# B6_32D_20230729.net
KiCad netlist of a schematic drawn in Altium Designer
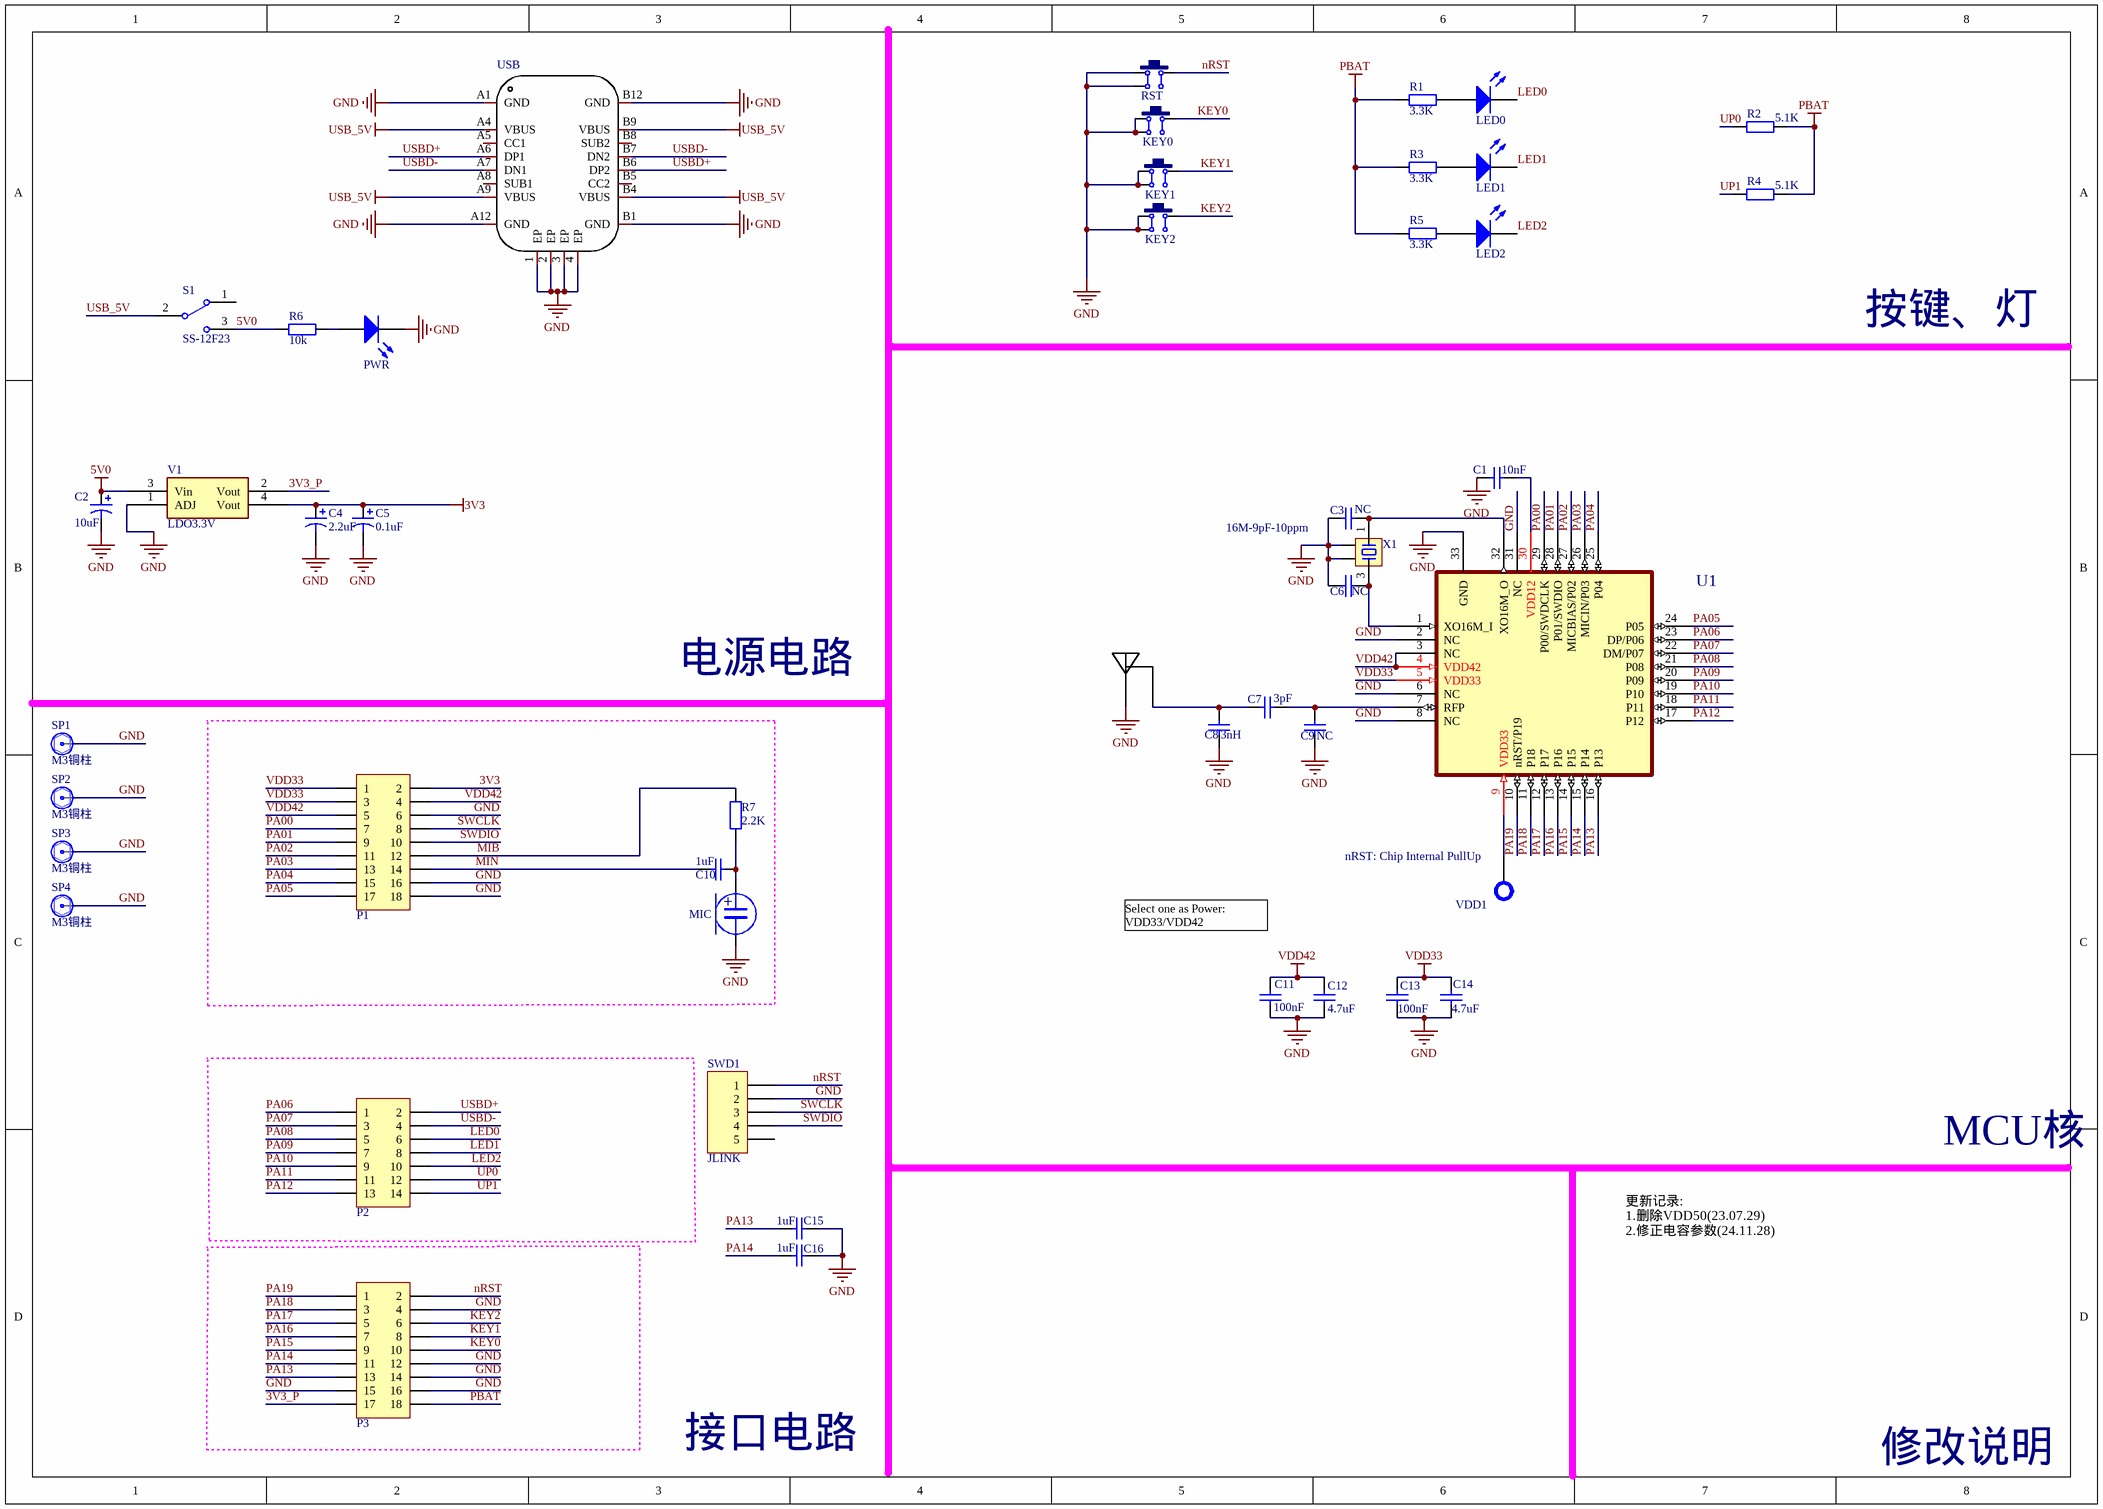
[diagram p0: B6_32D_20230729.SchDoc]

(export (version "E")
  (design (tool "Eeschema 10.0.6"))
  (components
    (comp (ref "ANT1")
      (value "ANT1")
      (footprint "常用2.4G天线7")
      (libsource (lib "HYBXX_Dragon") (part "ANT_PCB2"))
    )
    (comp (ref "C1")
      (value "10nF")
      (footprint "C0603")
      (description "Capacitor (Semiconductor SIM Model)")
      (libsource (lib "HYBXX_Dragon") (part "Cap"))
    )
    (comp (ref "C2")
      (value "10uF")
      (footprint "HYBXX_Dragon:C0603")
      (description "Polarized Capacitor (Surface Mount)")
      (fields (field (name "PUBLISHER") "Altium Limited"))
      (libsource (lib "HYBXX_Dragon") (part "Cap Pol3"))
    )
    (comp (ref "C3")
      (value "NC")
      (footprint "C0603")
      (description "Capacitor (Semiconductor SIM Model)")
      (libsource (lib "HYBXX_Dragon") (part "Cap"))
    )
    (comp (ref "C4")
      (value "2.2uF")
      (footprint "HYBXX_Dragon:C0603")
      (description "Polarized Capacitor (Surface Mount)")
      (fields (field (name "PUBLISHER") "Altium Limited"))
      (libsource (lib "HYBXX_Dragon") (part "Cap Pol3"))
    )
    (comp (ref "C5")
      (value "0.1uF")
      (footprint "HYBXX_Dragon:C0603")
      (description "Polarized Capacitor (Surface Mount)")
      (fields (field (name "PUBLISHER") "Altium Limited"))
      (libsource (lib "HYBXX_Dragon") (part "Cap Pol3"))
    )
    (comp (ref "C6")
      (value "NC")
      (footprint "C0603")
      (description "Capacitor (Semiconductor SIM Model)")
      (libsource (lib "HYBXX_Dragon") (part "Cap"))
    )
    (comp (ref "C7")
      (value "3pF")
      (footprint "C0402")
      (description "Capacitor (Semiconductor SIM Model)")
      (libsource (lib "HYBXX_Dragon") (part "Cap"))
    )
    (comp (ref "C8")
      (value "3nH")
      (footprint "C0402")
      (description "Capacitor (Semiconductor SIM Model)")
      (libsource (lib "HYBXX_Dragon") (part "Cap"))
    )
    (comp (ref "C9")
      (value "NC")
      (footprint "C0402")
      (description "Capacitor (Semiconductor SIM Model)")
      (libsource (lib "HYBXX_Dragon") (part "Cap"))
    )
    (comp (ref "C10")
      (value "1uF")
      (footprint "C0603")
      (description "Capacitor (Semiconductor SIM Model)")
      (libsource (lib "HYBXX_Dragon") (part "Cap"))
    )
    (comp (ref "C11")
      (value "100nF")
      (footprint "C0603")
      (description "Capacitor (Semiconductor SIM Model)")
      (libsource (lib "HYBXX_Dragon") (part "Cap"))
    )
    (comp (ref "C12")
      (value "4.7uF")
      (footprint "C0603")
      (description "Capacitor (Semiconductor SIM Model)")
      (libsource (lib "HYBXX_Dragon") (part "Cap"))
    )
    (comp (ref "C13")
      (value "100nF")
      (footprint "C0603")
      (description "Capacitor (Semiconductor SIM Model)")
      (fields (field (name "PUBLISHER") "Altium Limited"))
      (libsource (lib "Miscellaneous Devices") (part "Cap Semi"))
    )
    (comp (ref "C14")
      (value "4.7uF")
      (footprint "C0603")
      (description "Capacitor (Semiconductor SIM Model)")
      (libsource (lib "HYBXX_Dragon") (part "Cap"))
    )
    (comp (ref "C15")
      (value "1uF")
      (footprint "C0603")
      (description "Capacitor (Semiconductor SIM Model)")
      (libsource (lib "HYBXX_Dragon") (part "Cap"))
    )
    (comp (ref "C16")
      (value "1uF")
      (footprint "C0603")
      (description "Capacitor (Semiconductor SIM Model)")
      (libsource (lib "HYBXX_Dragon") (part "Cap"))
    )
    (comp (ref "KEY0")
      (value "6x6x5")
      (footprint "SW-SMD")
      (description "贴片6x6轻触开关")
      (fields (field (name "版权归属") "封装库来自淘宝 ID：黄晶宝石"))
      (libsource (lib "0.7 - 常用按键-开关") (part "TSW SMD-6x6"))
    )
    (comp (ref "KEY1")
      (value "6x6x5")
      (footprint "SW-SMD")
      (description "贴片6x6轻触开关")
      (fields (field (name "版权归属") "封装库来自淘宝 ID：黄晶宝石"))
      (libsource (lib "0.7 - 常用按键-开关") (part "TSW SMD-6x6"))
    )
    (comp (ref "KEY2")
      (value "6x6x5")
      (footprint "SW-SMD")
      (description "贴片6x6轻触开关")
      (fields (field (name "版权归属") "封装库来自淘宝 ID：黄晶宝石"))
      (libsource (lib "0.7 - 常用按键-开关") (part "TSW SMD-6x6"))
    )
    (comp (ref "LED0")
      (value "*")
      (footprint "LED_0603")
      (description "发光二极管")
      (libsource (lib "HYBXX_Dragon") (part "LED"))
    )
    (comp (ref "LED1")
      (value "*")
      (footprint "LED_0603")
      (description "发光二极管")
      (libsource (lib "HYBXX_Dragon") (part "LED"))
    )
    (comp (ref "LED2")
      (value "*")
      (footprint "LED_0603")
      (description "发光二极管")
      (libsource (lib "HYBXX_Dragon") (part "LED"))
    )
    (comp (ref "MIC")
      (value "MIC-6*5mm")
      (footprint "MIC-6*5.5mm")
      (description "电容麦克风")
      (fields (field (name "版权归属") "封装库来自淘宝 ID：黄晶宝石"))
      (libsource (lib "1.2 - 传感元件") (part "MIC1"))
    )
    (comp (ref "P1")
      (value "Header 2X11")
      (footprint "HDR2.54-LI-2x9P")
      (description "9*2P接插件")
      (fields (field (name "版权归属") "淘宝ID:黄晶宝石"))
      (libsource (lib "5.3 - 接插件-脚距2.54 (100mil) ") (part "Header 9X2"))
    )
    (comp (ref "P2")
      (value "Header 2X7")
      (footprint "HDR2.54-LI-2x7P")
      (description "7*2P接插件")
      (fields (field (name "版权归属") "封装库来自淘宝 ID：黄晶宝石"))
      (libsource (lib "5.3 - 接插件-脚距2.54 (100mil) ") (part "Header 7X2"))
    )
    (comp (ref "P3")
      (value "Header 2X11")
      (footprint "HDR2.54-LI-2x9P")
      (description "9*2P接插件")
      (fields (field (name "版权归属") "淘宝ID:黄晶宝石"))
      (libsource (lib "5.3 - 接插件-脚距2.54 (100mil) ") (part "Header 9X2"))
    )
    (comp (ref "PWR")
      (value "*")
      (footprint "LED_0603")
      (description "发光二极管")
      (libsource (lib "HYBXX_Dragon") (part "LED"))
    )
    (comp (ref "R1")
      (value "3.3K")
      (footprint "R 0603_L")
      (description "贴片电阻")
      (libsource (lib "HYBXX_Dragon") (part "Res"))
    )
    (comp (ref "R2")
      (value "5.1K")
      (footprint "R 0603_L")
      (description "贴片电阻")
      (libsource (lib "") (part "Res_1"))
    )
    (comp (ref "R3")
      (value "3.3K")
      (footprint "R 0603_L")
      (description "贴片电阻")
      (libsource (lib "HYBXX_Dragon") (part "Res"))
    )
    (comp (ref "R4")
      (value "5.1K")
      (footprint "R 0603_L")
      (description "贴片电阻")
      (libsource (lib "") (part "Res_1"))
    )
    (comp (ref "R5")
      (value "3.3K")
      (footprint "R 0603_L")
      (description "贴片电阻")
      (libsource (lib "HYBXX_Dragon") (part "Res"))
    )
    (comp (ref "R6")
      (value "10k")
      (footprint "RESC_0603")
      (description "贴片电阻")
      (libsource (lib "HYBXX_Dragon") (part "Res"))
    )
    (comp (ref "R7")
      (value "2.2K")
      (footprint "R 0603_L")
      (description "贴片电阻")
      (libsource (lib "") (part "Res_1"))
    )
    (comp (ref "RST")
      (value "6x6x5")
      (footprint "SW-SMD")
      (description "贴片6x6轻触开关")
      (fields (field (name "版权归属") "封装库来自淘宝 ID：黄晶宝石"))
      (libsource (lib "0.7 - 常用按键-开关") (part "TSW SMD-6x6"))
    )
    (comp (ref "S1")
      (value "SS-12F23")
      (footprint "SK12D07VG3")
      (description "1路波动开关")
      (fields (field (name "版权归属") "封装库来自淘宝 ID：黄晶宝石"))
      (libsource (lib "0.7 - 常用按键-开关") (part "SSW-1P"))
    )
    (comp (ref "SP1")
      (value "M3铜柱")
      (footprint "M3x21+6_L")
      (description "铜柱")
      (libsource (lib "4.1 - 未分类器件") (part "铜柱加头小焊盘"))
    )
    (comp (ref "SP2")
      (value "M3铜柱")
      (footprint "M3x21+6_L")
      (description "铜柱")
      (fields (field (name "版权归属") "封装库来自淘宝 ID：黄晶宝石"))
      (libsource (lib "4.1 - 未分类器件") (part "铜柱加头小焊盘"))
    )
    (comp (ref "SP3")
      (value "M3铜柱")
      (footprint "M3x21+6_L")
      (description "铜柱")
      (fields (field (name "版权归属") "封装库来自淘宝 ID：黄晶宝石"))
      (libsource (lib "4.1 - 未分类器件") (part "铜柱加头小焊盘"))
    )
    (comp (ref "SP4")
      (value "M3铜柱")
      (footprint "M3x21+6_L")
      (description "铜柱")
      (fields (field (name "版权归属") "封装库来自淘宝 ID：黄晶宝石"))
      (libsource (lib "4.1 - 未分类器件") (part "铜柱加头小焊盘"))
    )
    (comp (ref "SWD1")
      (value "JLINK")
      (footprint "HDR2.54-LI-5P")
      (description "Header, 5-Pin")
      (fields (field (name "PUBLISHER") "Altium Limited"))
      (libsource (lib "5.3 - 接插件-脚距2.54 (100mil) ") (part "Header 5"))
    )
    (comp (ref "U1")
      (value "C1_QFN32")
      (footprint "QFN32L_0404x0.75-0.40")
      (description "HY Dragon C 蓝牙芯片, QFN32_4x4")
      (libsource (lib "HYBXX_Dragon") (part "C1_QFN32"))
    )
    (comp (ref "USB")
      (value "KH-TYPE-C-16P")
      (footprint "USB-C-SMD_KH-TYPE-C-16P")
      (description "连接器类型:Type-C;标准:-;公母:母座;触点数量:16;端口数量:1;安装方式:卧贴;额定电流 - 电源:3A;工作温度范围:-40~+85;")
      (fields (field (name "MANUFACTURER") "kinghelm(金航标)"))
      (libsource (lib "altium-import") (part "root_0_KH-TYPE-C-16P_"))
    )
    (comp (ref "V1")
      (value "LDO3.3V")
      (footprint "SOT223_L")
      (description "LDO 可调节稳压芯片")
      (libsource (lib "HYBXX_Dragon") (part "AMS1117"))
    )
    (comp (ref "VDD1")
      (value "HOLE")
      (footprint "HYBXX_Dragon:TEST_PAD")
      (description "定位孔")
      (libsource (lib "HYBXX_Dragon") (part "HOLE"))
    )
    (comp (ref "X1")
      (value "16M-9pF-10ppm")
      (footprint "OSC3225-mini")
      (description "4脚无源晶振")
      (fields (field (name "版权归属") "封装库来自淘宝卖家 ID：黄晶宝石"))
      (libsource (lib "2.0 - 保险丝-晶振-光耦") (part "XTAL-4P"))
    )
  )
  (nets
    (net (code "1") (name "/3V3_P") (class "Default")
      (node (ref "P3") (pin "17") (pinfunction "17_17") (pintype "passive"))
      (node (ref "V1") (pin "2") (pinfunction "Vout_2") (pintype "passive"))
    )
    (net (code "2") (name "/KEY0") (class "Default")
      (node (ref "KEY0") (pin "2") (pinfunction "2_2") (pintype "passive"))
      (node (ref "P3") (pin "10") (pinfunction "10_10") (pintype "passive"))
    )
    (net (code "3") (name "/KEY1") (class "Default")
      (node (ref "KEY1") (pin "2") (pinfunction "2_2") (pintype "passive"))
      (node (ref "P3") (pin "8") (pinfunction "8_8") (pintype "passive"))
    )
    (net (code "4") (name "/KEY2") (class "Default")
      (node (ref "KEY2") (pin "2") (pinfunction "2_2") (pintype "passive"))
      (node (ref "P3") (pin "6") (pinfunction "6_6") (pintype "passive"))
    )
    (net (code "5") (name "/LED0") (class "Default")
      (node (ref "LED0") (pin "2") (pinfunction "K_2") (pintype "passive"))
      (node (ref "P2") (pin "6") (pinfunction "6_6") (pintype "passive"))
    )
    (net (code "6") (name "/LED1") (class "Default")
      (node (ref "LED1") (pin "2") (pinfunction "K_2") (pintype "passive"))
      (node (ref "P2") (pin "8") (pinfunction "8_8") (pintype "passive"))
    )
    (net (code "7") (name "/LED2") (class "Default")
      (node (ref "LED2") (pin "2") (pinfunction "K_2") (pintype "passive"))
      (node (ref "P2") (pin "10") (pinfunction "10_10") (pintype "passive"))
    )
    (net (code "8") (name "/MIB") (class "Default")
      (node (ref "P1") (pin "12") (pinfunction "12_12") (pintype "passive"))
      (node (ref "R7") (pin "1") (pinfunction "1_1") (pintype "passive"))
    )
    (net (code "9") (name "/MIN") (class "Default")
      (node (ref "C10") (pin "2") (pinfunction "2_2") (pintype "passive"))
      (node (ref "P1") (pin "14") (pinfunction "14_14") (pintype "passive"))
    )
    (net (code "10") (name "/PA00") (class "Default")
      (node (ref "P1") (pin "7") (pinfunction "7_7") (pintype "passive"))
      (node (ref "U1") (pin "29") (pinfunction "P00/SWDCLK_29") (pintype "bidirectional"))
    )
    (net (code "11") (name "/PA01") (class "Default")
      (node (ref "P1") (pin "9") (pinfunction "9_9") (pintype "passive"))
      (node (ref "U1") (pin "28") (pinfunction "P01/SWDIO_28") (pintype "bidirectional"))
    )
    (net (code "12") (name "/PA02") (class "Default")
      (node (ref "P1") (pin "11") (pinfunction "11_11") (pintype "passive"))
      (node (ref "U1") (pin "27") (pinfunction "MICBIAS/P02_27") (pintype "bidirectional"))
    )
    (net (code "13") (name "/PA03") (class "Default")
      (node (ref "P1") (pin "13") (pinfunction "13_13") (pintype "passive"))
      (node (ref "U1") (pin "26") (pinfunction "MICIN/P03_26") (pintype "bidirectional"))
    )
    (net (code "14") (name "/PA04") (class "Default")
      (node (ref "P1") (pin "15") (pinfunction "15_15") (pintype "passive"))
      (node (ref "U1") (pin "25") (pinfunction "P04_25") (pintype "bidirectional"))
    )
    (net (code "15") (name "/PA05") (class "Default")
      (node (ref "P1") (pin "17") (pinfunction "17_17") (pintype "passive"))
      (node (ref "U1") (pin "24") (pinfunction "P05_24") (pintype "bidirectional"))
    )
    (net (code "16") (name "/PA06") (class "Default")
      (node (ref "P2") (pin "1") (pinfunction "1_1") (pintype "passive"))
      (node (ref "U1") (pin "23") (pinfunction "DP/P06_23") (pintype "bidirectional"))
    )
    (net (code "17") (name "/PA07") (class "Default")
      (node (ref "P2") (pin "3") (pinfunction "3_3") (pintype "passive"))
      (node (ref "U1") (pin "22") (pinfunction "DM/P07_22") (pintype "bidirectional"))
    )
    (net (code "18") (name "/PA08") (class "Default")
      (node (ref "P2") (pin "5") (pinfunction "5_5") (pintype "passive"))
      (node (ref "U1") (pin "21") (pinfunction "P08_21") (pintype "bidirectional"))
    )
    (net (code "19") (name "/PA09") (class "Default")
      (node (ref "P2") (pin "7") (pinfunction "7_7") (pintype "passive"))
      (node (ref "U1") (pin "20") (pinfunction "P09_20") (pintype "bidirectional"))
    )
    (net (code "20") (name "/PA10") (class "Default")
      (node (ref "P2") (pin "9") (pinfunction "9_9") (pintype "passive"))
      (node (ref "U1") (pin "19") (pinfunction "P10_19") (pintype "bidirectional"))
    )
    (net (code "21") (name "/PA11") (class "Default")
      (node (ref "P2") (pin "11") (pinfunction "11_11") (pintype "passive"))
      (node (ref "U1") (pin "18") (pinfunction "P11_18") (pintype "bidirectional"))
    )
    (net (code "22") (name "/PA12") (class "Default")
      (node (ref "P2") (pin "13") (pinfunction "13_13") (pintype "passive"))
      (node (ref "U1") (pin "17") (pinfunction "P12_17") (pintype "bidirectional"))
    )
    (net (code "23") (name "/PA13") (class "Default")
      (node (ref "C15") (pin "2") (pinfunction "2_2") (pintype "passive"))
      (node (ref "P3") (pin "13") (pinfunction "13_13") (pintype "passive"))
      (node (ref "U1") (pin "16") (pinfunction "P13_16") (pintype "bidirectional"))
    )
    (net (code "24") (name "/PA14") (class "Default")
      (node (ref "C16") (pin "2") (pinfunction "2_2") (pintype "passive"))
      (node (ref "P3") (pin "11") (pinfunction "11_11") (pintype "passive"))
      (node (ref "U1") (pin "15") (pinfunction "P14_15") (pintype "bidirectional"))
    )
    (net (code "25") (name "/PA15") (class "Default")
      (node (ref "P3") (pin "9") (pinfunction "9_9") (pintype "passive"))
      (node (ref "U1") (pin "14") (pinfunction "P15_14") (pintype "bidirectional"))
    )
    (net (code "26") (name "/PA16") (class "Default")
      (node (ref "P3") (pin "7") (pinfunction "7_7") (pintype "passive"))
      (node (ref "U1") (pin "13") (pinfunction "P16_13") (pintype "bidirectional"))
    )
    (net (code "27") (name "/PA17") (class "Default")
      (node (ref "P3") (pin "5") (pinfunction "5_5") (pintype "passive"))
      (node (ref "U1") (pin "12") (pinfunction "P17_12") (pintype "bidirectional"))
    )
    (net (code "28") (name "/PA18") (class "Default")
      (node (ref "P3") (pin "3") (pinfunction "3_3") (pintype "passive"))
      (node (ref "U1") (pin "11") (pinfunction "P18_11") (pintype "bidirectional"))
    )
    (net (code "29") (name "/PA19") (class "Default")
      (node (ref "P3") (pin "1") (pinfunction "1_1") (pintype "passive"))
      (node (ref "U1") (pin "10") (pinfunction "nRST/P19_10") (pintype "bidirectional"))
    )
    (net (code "30") (name "/SWCLK") (class "Default")
      (node (ref "P1") (pin "8") (pinfunction "8_8") (pintype "passive"))
      (node (ref "SWD1") (pin "3") (pinfunction "3_3") (pintype "passive"))
    )
    (net (code "31") (name "/SWDIO") (class "Default")
      (node (ref "P1") (pin "10") (pinfunction "10_10") (pintype "passive"))
      (node (ref "SWD1") (pin "4") (pinfunction "4_4") (pintype "passive"))
    )
    (net (code "32") (name "/UP0") (class "Default")
      (node (ref "P2") (pin "12") (pinfunction "12_12") (pintype "passive"))
      (node (ref "R2") (pin "2") (pinfunction "2_2") (pintype "passive"))
    )
    (net (code "33") (name "/UP1") (class "Default")
      (node (ref "P2") (pin "14") (pinfunction "14_14") (pintype "passive"))
      (node (ref "R4") (pin "2") (pinfunction "2_2") (pintype "passive"))
    )
    (net (code "34") (name "/USBD+") (class "Default")
      (node (ref "P2") (pin "2") (pinfunction "2_2") (pintype "passive"))
      (node (ref "USB") (pin "A6") (pinfunction "DP1_A6") (pintype "passive"))
      (node (ref "USB") (pin "B6") (pinfunction "DP2_B6") (pintype "passive"))
    )
    (net (code "35") (name "/USBD-") (class "Default")
      (node (ref "P2") (pin "4") (pinfunction "4_4") (pintype "passive"))
      (node (ref "USB") (pin "A7") (pinfunction "DN1_A7") (pintype "passive"))
      (node (ref "USB") (pin "B7") (pinfunction "DN2_B7") (pintype "passive"))
    )
    (net (code "36") (name "/nRST") (class "Default")
      (node (ref "P3") (pin "2") (pinfunction "2_2") (pintype "passive"))
      (node (ref "RST") (pin "2") (pinfunction "2_2") (pintype "passive"))
      (node (ref "SWD1") (pin "1") (pinfunction "1_1") (pintype "passive"))
    )
    (net (code "37") (name "3V3") (class "Default")
      (node (ref "C4") (pin "1") (pinfunction "1_1") (pintype "passive"))
      (node (ref "C5") (pin "1") (pinfunction "1_1") (pintype "passive"))
      (node (ref "P1") (pin "2") (pinfunction "2_2") (pintype "passive"))
      (node (ref "V1") (pin "4") (pinfunction "Vout_4") (pintype "passive"))
    )
    (net (code "38") (name "5V0") (class "Default")
      (node (ref "C2") (pin "1") (pinfunction "1_1") (pintype "passive"))
      (node (ref "R6") (pin "1") (pinfunction "1_1") (pintype "passive"))
      (node (ref "S1") (pin "3") (pinfunction "3_3") (pintype "passive"))
      (node (ref "V1") (pin "3") (pinfunction "Vin_3") (pintype "passive"))
    )
    (net (code "39") (name "GND") (class "Default")
      (node (ref "ANT1") (pin "1") (pinfunction "1_1") (pintype "passive"))
      (node (ref "C1") (pin "2") (pinfunction "2_2") (pintype "passive"))
      (node (ref "C11") (pin "1") (pinfunction "1_1") (pintype "passive"))
      (node (ref "C12") (pin "1") (pinfunction "1_1") (pintype "passive"))
      (node (ref "C13") (pin "1") (pinfunction "1_1") (pintype "passive"))
      (node (ref "C14") (pin "2") (pinfunction "2_2") (pintype "passive"))
      (node (ref "C15") (pin "1") (pinfunction "1_1") (pintype "passive"))
      (node (ref "C16") (pin "1") (pinfunction "1_1") (pintype "passive"))
      (node (ref "C2") (pin "2") (pinfunction "2_2") (pintype "passive"))
      (node (ref "C3") (pin "1") (pinfunction "1_1") (pintype "passive"))
      (node (ref "C4") (pin "2") (pinfunction "2_2") (pintype "passive"))
      (node (ref "C5") (pin "2") (pinfunction "2_2") (pintype "passive"))
      (node (ref "C6") (pin "2") (pinfunction "2_2") (pintype "passive"))
      (node (ref "C8") (pin "2") (pinfunction "2_2") (pintype "passive"))
      (node (ref "C9") (pin "2") (pinfunction "2_2") (pintype "passive"))
      (node (ref "KEY0") (pin "1") (pinfunction "1_1") (pintype "passive"))
      (node (ref "KEY0") (pin "4") (pinfunction "4_4") (pintype "passive"))
      (node (ref "KEY1") (pin "1") (pinfunction "1_1") (pintype "passive"))
      (node (ref "KEY1") (pin "4") (pinfunction "4_4") (pintype "passive"))
      (node (ref "KEY2") (pin "1") (pinfunction "1_1") (pintype "passive"))
      (node (ref "KEY2") (pin "4") (pinfunction "4_4") (pintype "passive"))
      (node (ref "MIC") (pin "2") (pinfunction "2_2") (pintype "passive"))
      (node (ref "P1") (pin "16") (pinfunction "16_16") (pintype "passive"))
      (node (ref "P1") (pin "18") (pinfunction "18_18") (pintype "passive"))
      (node (ref "P1") (pin "6") (pinfunction "6_6") (pintype "passive"))
      (node (ref "P3") (pin "12") (pinfunction "12_12") (pintype "passive"))
      (node (ref "P3") (pin "14") (pinfunction "14_14") (pintype "passive"))
      (node (ref "P3") (pin "15") (pinfunction "15_15") (pintype "passive"))
      (node (ref "P3") (pin "16") (pinfunction "16_16") (pintype "passive"))
      (node (ref "P3") (pin "4") (pinfunction "4_4") (pintype "passive"))
      (node (ref "PWR") (pin "2") (pinfunction "K_2") (pintype "passive"))
      (node (ref "RST") (pin "1") (pinfunction "1_1") (pintype "passive"))
      (node (ref "RST") (pin "4") (pinfunction "4_4") (pintype "passive"))
      (node (ref "SP1") (pin "1") (pinfunction "1_1") (pintype "passive"))
      (node (ref "SP2") (pin "1") (pinfunction "1_1") (pintype "passive"))
      (node (ref "SP3") (pin "1") (pinfunction "1_1") (pintype "passive"))
      (node (ref "SP4") (pin "1") (pinfunction "1_1") (pintype "passive"))
      (node (ref "SWD1") (pin "2") (pinfunction "2_2") (pintype "passive"))
      (node (ref "U1") (pin "2") (pinfunction "NC_2") (pintype "passive"))
      (node (ref "U1") (pin "31") (pinfunction "NC_31") (pintype "passive"))
      (node (ref "U1") (pin "33") (pinfunction "GND_33") (pintype "passive"))
      (node (ref "U1") (pin "6") (pinfunction "NC_6") (pintype "passive"))
      (node (ref "U1") (pin "8") (pinfunction "NC_8") (pintype "passive"))
      (node (ref "USB") (pin "1") (pinfunction "EP_1") (pintype "passive"))
      (node (ref "USB") (pin "2") (pinfunction "EP_2") (pintype "passive"))
      (node (ref "USB") (pin "3") (pinfunction "EP_3") (pintype "passive"))
      (node (ref "USB") (pin "4") (pinfunction "EP_4") (pintype "passive"))
      (node (ref "USB") (pin "A1") (pinfunction "GND_A1") (pintype "passive"))
      (node (ref "USB") (pin "A12") (pinfunction "GND_A12") (pintype "passive"))
      (node (ref "USB") (pin "B1") (pinfunction "GND_B1") (pintype "passive"))
      (node (ref "USB") (pin "B12") (pinfunction "GND_B12") (pintype "passive"))
      (node (ref "V1") (pin "1") (pinfunction "ADJ_1") (pintype "passive"))
      (node (ref "X1") (pin "2") (pinfunction "2_2") (pintype "passive"))
      (node (ref "X1") (pin "4") (pinfunction "4_4") (pintype "passive"))
    )
    (net (code "40") (name "Net-(ANT1-Pad2)") (class "Default")
      (node (ref "ANT1") (pin "2") (pinfunction "2_2") (pintype "passive"))
      (node (ref "C7") (pin "2") (pinfunction "2_2") (pintype "passive"))
      (node (ref "C8") (pin "1") (pinfunction "1_1") (pintype "passive"))
    )
    (net (code "41") (name "Net-(C10-Pad1)") (class "Default")
      (node (ref "C10") (pin "1") (pinfunction "1_1") (pintype "passive"))
      (node (ref "MIC") (pin "1") (pinfunction "1_1") (pintype "passive"))
      (node (ref "R7") (pin "2") (pinfunction "2_2") (pintype "passive"))
    )
    (net (code "42") (name "Net-(LED0-A)") (class "Default")
      (node (ref "LED0") (pin "1") (pinfunction "A_1") (pintype "passive"))
      (node (ref "R1") (pin "2") (pinfunction "2_2") (pintype "passive"))
    )
    (net (code "43") (name "Net-(LED1-A)") (class "Default")
      (node (ref "LED1") (pin "1") (pinfunction "A_1") (pintype "passive"))
      (node (ref "R3") (pin "2") (pinfunction "2_2") (pintype "passive"))
    )
    (net (code "44") (name "Net-(LED2-A)") (class "Default")
      (node (ref "LED2") (pin "1") (pinfunction "A_1") (pintype "passive"))
      (node (ref "R5") (pin "2") (pinfunction "2_2") (pintype "passive"))
    )
    (net (code "45") (name "Net-(PWR-A)") (class "Default")
      (node (ref "PWR") (pin "1") (pinfunction "A_1") (pintype "passive"))
      (node (ref "R6") (pin "2") (pinfunction "2_2") (pintype "passive"))
    )
    (net (code "46") (name "Net-(U1-RFP)") (class "Default")
      (node (ref "C7") (pin "1") (pinfunction "1_1") (pintype "passive"))
      (node (ref "C9") (pin "1") (pinfunction "1_1") (pintype "passive"))
      (node (ref "U1") (pin "7") (pinfunction "RFP_7") (pintype "bidirectional"))
    )
    (net (code "47") (name "Net-(U1-VDD12)") (class "Default")
      (node (ref "C1") (pin "1") (pinfunction "1_1") (pintype "passive"))
      (node (ref "U1") (pin "30") (pinfunction "VDD12_30") (pintype "passive"))
    )
    (net (code "48") (name "Net-(U1-XO16M_I)") (class "Default")
      (node (ref "C6") (pin "1") (pinfunction "1_1") (pintype "passive"))
      (node (ref "U1") (pin "1") (pinfunction "XO16M_I_1") (pintype "input"))
      (node (ref "X1") (pin "3") (pinfunction "3_3") (pintype "passive"))
    )
    (net (code "49") (name "Net-(U1-XO16M_O)") (class "Default")
      (node (ref "C3") (pin "2") (pinfunction "2_2") (pintype "passive"))
      (node (ref "U1") (pin "32") (pinfunction "XO16M_O_32") (pintype "output"))
      (node (ref "X1") (pin "1") (pinfunction "1_1") (pintype "passive"))
    )
    (net (code "50") (name "Net-(VDD1-HOLE)") (class "Default")
      (node (ref "U1") (pin "9") (pinfunction "VDD33_9") (pintype "input"))
      (node (ref "VDD1") (pin "1") (pinfunction "HOLE_1") (pintype "passive"))
    )
    (net (code "51") (name "PBAT") (class "Default")
      (node (ref "P3") (pin "18") (pinfunction "18_18") (pintype "passive"))
      (node (ref "R1") (pin "1") (pinfunction "1_1") (pintype "passive"))
      (node (ref "R2") (pin "1") (pinfunction "1_1") (pintype "passive"))
      (node (ref "R3") (pin "1") (pinfunction "1_1") (pintype "passive"))
      (node (ref "R4") (pin "1") (pinfunction "1_1") (pintype "passive"))
      (node (ref "R5") (pin "1") (pinfunction "1_1") (pintype "passive"))
    )
    (net (code "52") (name "USB_5V") (class "Default")
      (node (ref "S1") (pin "2") (pinfunction "2_2") (pintype "passive"))
      (node (ref "USB") (pin "A4") (pinfunction "VBUS_A4") (pintype "passive"))
      (node (ref "USB") (pin "A9") (pinfunction "VBUS_A9") (pintype "passive"))
      (node (ref "USB") (pin "B4") (pinfunction "VBUS_B4") (pintype "passive"))
      (node (ref "USB") (pin "B9") (pinfunction "VBUS_B9") (pintype "passive"))
    )
    (net (code "53") (name "VDD33") (class "Default")
      (node (ref "C13") (pin "2") (pinfunction "2_2") (pintype "passive"))
      (node (ref "C14") (pin "1") (pinfunction "1_1") (pintype "passive"))
      (node (ref "P1") (pin "1") (pinfunction "1_1") (pintype "passive"))
      (node (ref "P1") (pin "3") (pinfunction "3_3") (pintype "passive"))
      (node (ref "U1") (pin "5") (pinfunction "VDD33_5") (pintype "input"))
    )
    (net (code "54") (name "VDD42") (class "Default")
      (node (ref "C11") (pin "2") (pinfunction "2_2") (pintype "passive"))
      (node (ref "C12") (pin "2") (pinfunction "2_2") (pintype "passive"))
      (node (ref "P1") (pin "4") (pinfunction "4_4") (pintype "passive"))
      (node (ref "P1") (pin "5") (pinfunction "5_5") (pintype "passive"))
      (node (ref "U1") (pin "3") (pinfunction "NC_3") (pintype "passive"))
      (node (ref "U1") (pin "4") (pinfunction "VDD42_4") (pintype "input"))
    )
    (net (code "55") (name "unconnected-(KEY0-Pad3)") (class "Default")
      (node (ref "KEY0") (pin "3") (pinfunction "3_3") (pintype "passive"))
    )
    (net (code "56") (name "unconnected-(KEY1-Pad3)") (class "Default")
      (node (ref "KEY1") (pin "3") (pinfunction "3_3") (pintype "passive"))
    )
    (net (code "57") (name "unconnected-(KEY2-Pad3)") (class "Default")
      (node (ref "KEY2") (pin "3") (pinfunction "3_3") (pintype "passive"))
    )
    (net (code "58") (name "unconnected-(RST-Pad3)") (class "Default")
      (node (ref "RST") (pin "3") (pinfunction "3_3") (pintype "passive"))
    )
    (net (code "59") (name "unconnected-(S1-Pad1)") (class "Default")
      (node (ref "S1") (pin "1") (pinfunction "1_1") (pintype "passive"))
    )
    (net (code "60") (name "unconnected-(SWD1-Pad5)") (class "Default")
      (node (ref "SWD1") (pin "5") (pinfunction "5_5") (pintype "passive"))
    )
    (net (code "61") (name "unconnected-(USB-CC1-PadA5)") (class "Default")
      (node (ref "USB") (pin "A5") (pinfunction "CC1_A5") (pintype "passive"))
    )
    (net (code "62") (name "unconnected-(USB-CC2-PadB5)") (class "Default")
      (node (ref "USB") (pin "B5") (pinfunction "CC2_B5") (pintype "passive"))
    )
    (net (code "63") (name "unconnected-(USB-SUB1-PadA8)") (class "Default")
      (node (ref "USB") (pin "A8") (pinfunction "SUB1_A8") (pintype "passive"))
    )
    (net (code "64") (name "unconnected-(USB-SUB2-PadB8)") (class "Default")
      (node (ref "USB") (pin "B8") (pinfunction "SUB2_B8") (pintype "passive"))
    )
  )
)
